# miditendo_rev4.net
KiCad netlist of a schematic drawn in EAGLE
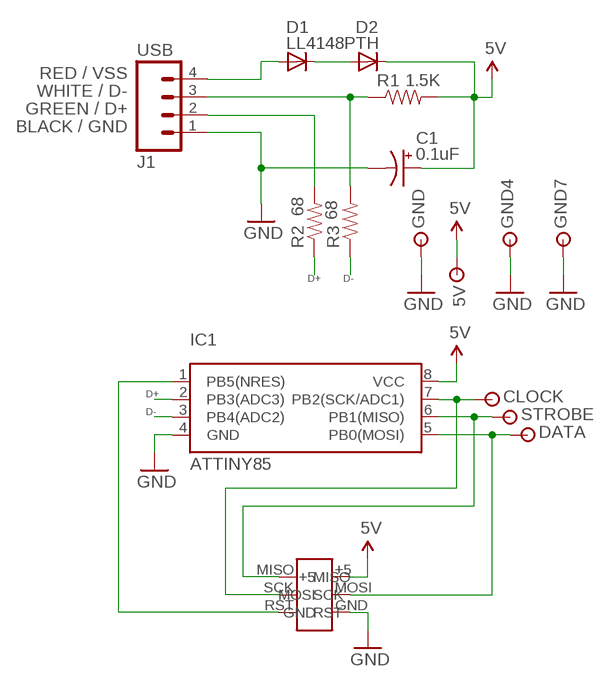
[diagram p0: schematic, sheet 1]

(export (version "E")
  (design (tool "Eeschema 10.0.6"))
  (components
    (comp (ref "5V")
      (value "WIRE_JOINT")
      (footprint "eagle-import:THSOLDERPOINT")
      (libsource (lib "eagle-import") (part "WIRE_JOINT"))
    )
    (comp (ref "C1")
      (value "0.1uF")
      (footprint "eagle-import:POLCAP_2.54")
      (libsource (lib "eagle-import") (part "POLARIZEDCAPACITORTH_2.54"))
    )
    (comp (ref "CLOCK")
      (value "WIRE_JOINT")
      (footprint "eagle-import:THSOLDERPOINT")
      (libsource (lib "eagle-import") (part "WIRE_JOINT"))
    )
    (comp (ref "D1")
      (value "LL4148PTH")
      (footprint "eagle-import:1N4148-PTH")
      (libsource (lib "eagle-import") (part "LL4148PTH"))
    )
    (comp (ref "D2")
      (value "LL4148PTH")
      (footprint "eagle-import:1N4148-PTH")
      (libsource (lib "eagle-import") (part "LL4148PTH"))
    )
    (comp (ref "DATA")
      (value "WIRE_JOINT")
      (footprint "eagle-import:THSOLDERPOINT")
      (libsource (lib "eagle-import") (part "WIRE_JOINT"))
    )
    (comp (ref "GND")
      (value "WIRE_JOINT")
      (footprint "eagle-import:THSOLDERPOINT")
      (libsource (lib "eagle-import") (part "WIRE_JOINT"))
    )
    (comp (ref "GND4")
      (value "WIRE_JOINT")
      (footprint "eagle-import:THSOLDERPOINT")
      (libsource (lib "eagle-import") (part "WIRE_JOINT"))
    )
    (comp (ref "GND7")
      (value "WIRE_JOINT")
      (footprint "eagle-import:THSOLDERPOINT")
      (libsource (lib "eagle-import") (part "WIRE_JOINT"))
    )
    (comp (ref "IC1")
      (value "ATTINY85")
      (footprint "eagle-import:DIP8")
      (libsource (lib "eagle-import") (part "ATTINY85DIP"))
    )
    (comp (ref "R1")
      (value "1.5K")
      (footprint "eagle-import:0805")
      (libsource (lib "eagle-import") (part "RESISTOR0805"))
    )
    (comp (ref "R2")
      (value "68")
      (footprint "eagle-import:0805")
      (libsource (lib "eagle-import") (part "RESISTOR0805"))
    )
    (comp (ref "R3")
      (value "68")
      (footprint "eagle-import:0805")
      (libsource (lib "eagle-import") (part "RESISTOR0805"))
    )
    (comp (ref "STROBE")
      (value "WIRE_JOINT")
      (footprint "eagle-import:THSOLDERPOINT")
      (libsource (lib "eagle-import") (part "WIRE_JOINT"))
    )
    (comp (ref "U$1")
      (value "ICSPSMD")
      (footprint "eagle-import:ICSP_SMD")
      (libsource (lib "eagle-import") (part "ICSPSMD"))
    )
    (comp (ref "USB")
      (value "J1")
      (footprint "eagle-import:1X04-SMD")
      (libsource (lib "eagle-import") (part "M04SMD"))
    )
  )
  (nets
    (net (code "1") (name "/D+") (class "Default")
      (node (ref "IC1") (pin "2") (pinfunction "PB3(ADC3)_2") (pintype "bidirectional"))
      (node (ref "R2") (pin "1") (pinfunction "1_1") (pintype "passive"))
    )
    (net (code "2") (name "/D-") (class "Default")
      (node (ref "IC1") (pin "3") (pinfunction "PB4(ADC2)_3") (pintype "bidirectional"))
      (node (ref "R3") (pin "1") (pinfunction "1_1") (pintype "passive"))
    )
    (net (code "3") (name "5V") (class "Default")
      (node (ref "5V") (pin "P$1") (pinfunction "P$1_P$1") (pintype "passive"))
      (node (ref "C1") (pin "P") (pinfunction "+_P") (pintype "passive"))
      (node (ref "D2") (pin "C") (pinfunction "C_C") (pintype "passive"))
      (node (ref "IC1") (pin "8") (pinfunction "VCC_8") (pintype "bidirectional"))
      (node (ref "R1") (pin "2") (pinfunction "2_2") (pintype "passive"))
      (node (ref "U$1") (pin "+5") (pinfunction "+5_+5") (pintype "bidirectional"))
    )
    (net (code "4") (name "GND") (class "Default")
      (node (ref "C1") (pin "N") (pinfunction "-_N") (pintype "passive"))
      (node (ref "GND") (pin "P$1") (pinfunction "P$1_P$1") (pintype "passive"))
      (node (ref "GND4") (pin "P$1") (pinfunction "P$1_P$1") (pintype "passive"))
      (node (ref "GND7") (pin "P$1") (pinfunction "P$1_P$1") (pintype "passive"))
      (node (ref "IC1") (pin "4") (pinfunction "GND_4") (pintype "bidirectional"))
      (node (ref "U$1") (pin "GND") (pinfunction "GND_GND") (pintype "bidirectional"))
      (node (ref "USB") (pin "1") (pinfunction "1_1") (pintype "passive"))
    )
    (net (code "5") (name "Net-(D1-PadA)") (class "Default")
      (node (ref "D1") (pin "A") (pinfunction "A_A") (pintype "passive"))
      (node (ref "USB") (pin "4") (pinfunction "4_4") (pintype "passive"))
    )
    (net (code "6") (name "Net-(D1-PadC)") (class "Default")
      (node (ref "D1") (pin "C") (pinfunction "C_C") (pintype "passive"))
      (node (ref "D2") (pin "A") (pinfunction "A_A") (pintype "passive"))
    )
    (net (code "7") (name "Net-(IC1-PB0(MOSI))") (class "Default")
      (node (ref "DATA") (pin "P$1") (pinfunction "P$1_P$1") (pintype "passive"))
      (node (ref "IC1") (pin "5") (pinfunction "PB0(MOSI)_5") (pintype "bidirectional"))
      (node (ref "U$1") (pin "MOSI") (pinfunction "MOSI_MOSI") (pintype "bidirectional"))
    )
    (net (code "8") (name "Net-(IC1-PB1(MISO))") (class "Default")
      (node (ref "IC1") (pin "6") (pinfunction "PB1(MISO)_6") (pintype "bidirectional"))
      (node (ref "STROBE") (pin "P$1") (pinfunction "P$1_P$1") (pintype "passive"))
      (node (ref "U$1") (pin "MISO") (pinfunction "MISO_MISO") (pintype "bidirectional"))
    )
    (net (code "9") (name "Net-(IC1-PB2(SCK{slash}ADC1))") (class "Default")
      (node (ref "CLOCK") (pin "P$1") (pinfunction "P$1_P$1") (pintype "passive"))
      (node (ref "IC1") (pin "7") (pinfunction "PB2(SCK/ADC1)_7") (pintype "bidirectional"))
      (node (ref "U$1") (pin "SCK") (pinfunction "SCK_SCK") (pintype "bidirectional"))
    )
    (net (code "10") (name "Net-(IC1-PB5(NRES))") (class "Default")
      (node (ref "IC1") (pin "1") (pinfunction "PB5(NRES)_1") (pintype "bidirectional"))
      (node (ref "U$1") (pin "RST") (pinfunction "RST_RST") (pintype "bidirectional"))
    )
    (net (code "11") (name "Net-(R1-Pad1)") (class "Default")
      (node (ref "R1") (pin "1") (pinfunction "1_1") (pintype "passive"))
      (node (ref "R3") (pin "2") (pinfunction "2_2") (pintype "passive"))
      (node (ref "USB") (pin "3") (pinfunction "3_3") (pintype "passive"))
    )
    (net (code "12") (name "Net-(R2-Pad2)") (class "Default")
      (node (ref "R2") (pin "2") (pinfunction "2_2") (pintype "passive"))
      (node (ref "USB") (pin "2") (pinfunction "2_2") (pintype "passive"))
    )
  )
)
